# part5.net
KiCad netlist of a schematic drawn in Altium Designer
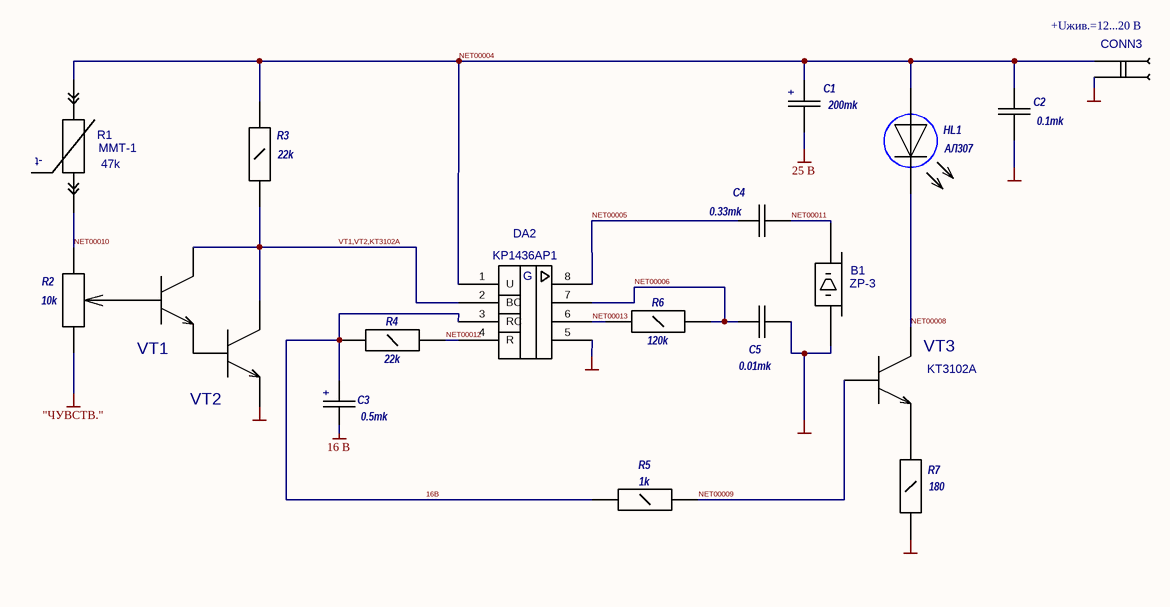
[diagram p0: part5.SCHDOC]

(export (version "E")
  (design (tool "Eeschema 10.0.6"))
  (components
    (comp (ref "B1") (value "ZP-3") (footprint "ЗП-3") (libsource (lib "*") (part "ZP-3")))
    (comp (ref "C1")
      (value "200mk")
      (footprint "К50-29 (17Х6)")
      (description "K50-29 (1;2,2;4,7;10;22 MK)")
      (libsource (lib "*") (part "K50-29 (1;2,2;4,7;10;22 MK)"))
    )
    (comp (ref "C2")
      (value "0.1mk")
      (footprint "K71-6 (10X4)")
      (description "K71-6 (5-30 МК)")
      (libsource (lib "*") (part "K71-6 (5-30 МК)"))
    )
    (comp (ref "C3")
      (value "0.5mk")
      (footprint "К50-29 (17Х6)")
      (description "K50-29 (1;2,2;4,7;10;22 MK)")
      (libsource (lib "*") (part "K50-29 (1;2,2;4,7;10;22 MK)"))
    )
    (comp (ref "C4")
      (value "0.33mk")
      (footprint "K71-6 (10X4)")
      (description "K71-6 (5-30 МК)")
      (libsource (lib "*") (part "K71-6 (5-30 МК)"))
    )
    (comp (ref "C5")
      (value "0.01mk")
      (footprint "K71-6 (10X4)")
      (description "K71-6 (5-30 МК)")
      (libsource (lib "*") (part "K71-6 (5-30 МК)"))
    )
    (comp (ref "CONN3")
      (value "+Uжив.=12...20 В")
      (footprint "CONN2X")
      (description "CONN2X")
      (libsource (lib "*") (part "CONN2X"))
    )
    (comp (ref "DA2") (value "KP1436AP1") (footprint "КР1436АП1") (libsource (lib "*") (part "KP1436AP1")))
    (comp (ref "HL1") (value "АЛ307") (footprint "АЛ307") (libsource (lib "*") (part "АЛ307")))
    (comp (ref "R1")
      (value "MMT-1")
      (footprint "MMT-1")
      (fields (field (name "ALTIUM_VALUE") "47k"))
      (libsource (lib "*") (part "MMT-1"))
    )
    (comp (ref "R2")
      (value "10k")
      (footprint "СП3-38В")
      (description "СП3-38В")
      (libsource (lib "*") (part "СП3-38В"))
    )
    (comp (ref "R3")
      (value "22k")
      (footprint "МЛТ(0.25)")
      (description "МЛТ(0.25)")
      (libsource (lib "*") (part "МЛТ(0.25)"))
    )
    (comp (ref "R4")
      (value "22k")
      (footprint "МЛТ(0.25)")
      (description "МЛТ(0.25)")
      (libsource (lib "*") (part "МЛТ(0.25)"))
    )
    (comp (ref "R5")
      (value "1k")
      (footprint "МЛТ(0.25)")
      (description "МЛТ(0.25)")
      (libsource (lib "*") (part "МЛТ(0.25)"))
    )
    (comp (ref "R6")
      (value "120k")
      (footprint "МЛТ(0.25)")
      (description "МЛТ(0.25)")
      (libsource (lib "*") (part "МЛТ(0.25)"))
    )
    (comp (ref "R7")
      (value "180")
      (footprint "МЛТ(0.25)")
      (description "МЛТ(0.25)")
      (libsource (lib "*") (part "МЛТ(0.25)"))
    )
    (comp (ref "VT1") (value "KT3102A") (footprint "KT3102A") (libsource (lib "*") (part "KT3102A")))
    (comp (ref "VT2") (value "KT3102A") (footprint "KT3102A") (libsource (lib "*") (part "KT3102A")))
    (comp (ref "VT3") (value "KT3102A") (footprint "KT3102A") (libsource (lib "*") (part "KT3102A")))
  )
  (nets
    (net (code "1") (name "\"ЧУВСТВ.\"") (class "Default")
      (node (ref "R2") (pin "2") (pinfunction "2_2") (pintype "passive"))
    )
    (net (code "2") (name "/16B") (class "Default")
      (node (ref "C3") (pin "2") (pinfunction "2_2") (pintype "passive"))
      (node (ref "DA2") (pin "3") (pinfunction "RC_3") (pintype "passive"))
      (node (ref "R4") (pin "1") (pinfunction "1_1") (pintype "passive"))
      (node (ref "R5") (pin "1") (pinfunction "1_1") (pintype "passive"))
    )
    (net (code "3") (name "/NET00004") (class "Default")
      (node (ref "C1") (pin "2") (pinfunction "2_2") (pintype "passive"))
      (node (ref "C2") (pin "2") (pinfunction "2_2") (pintype "passive"))
      (node (ref "CONN3") (pin "1") (pintype "passive"))
      (node (ref "DA2") (pin "1") (pinfunction "U_1") (pintype "passive"))
      (node (ref "HL1") (pin "1") (pinfunction "1_1") (pintype "passive"))
      (node (ref "R1") (pin "2") (pinfunction "2_2") (pintype "passive"))
      (node (ref "R3") (pin "1") (pinfunction "1_1") (pintype "passive"))
    )
    (net (code "4") (name "/NET00005") (class "Default")
      (node (ref "C4") (pin "2") (pinfunction "2_2") (pintype "passive"))
      (node (ref "DA2") (pin "8") (pintype "passive"))
    )
    (net (code "5") (name "/NET00006") (class "Default")
      (node (ref "C5") (pin "2") (pinfunction "2_2") (pintype "passive"))
      (node (ref "DA2") (pin "7") (pintype "passive"))
      (node (ref "R6") (pin "2") (pinfunction "2_2") (pintype "passive"))
    )
    (net (code "6") (name "/NET00008") (class "Default")
      (node (ref "HL1") (pin "2") (pinfunction "2_2") (pintype "passive"))
      (node (ref "VT3") (pin "3") (pinfunction "K_3") (pintype "passive"))
    )
    (net (code "7") (name "/NET00009") (class "Default")
      (node (ref "R5") (pin "2") (pinfunction "2_2") (pintype "passive"))
      (node (ref "VT3") (pin "2") (pinfunction "B_2") (pintype "passive"))
    )
    (net (code "8") (name "/NET00010") (class "Default")
      (node (ref "R1") (pin "1") (pinfunction "1_1") (pintype "passive"))
      (node (ref "R2") (pin "1") (pinfunction "1_1") (pintype "passive"))
    )
    (net (code "9") (name "/NET00011") (class "Default")
      (node (ref "B1") (pin "1") (pinfunction "1_1") (pintype "passive"))
      (node (ref "C4") (pin "1") (pinfunction "1_1") (pintype "passive"))
    )
    (net (code "10") (name "/NET00012") (class "Default")
      (node (ref "DA2") (pin "4") (pinfunction "R_4") (pintype "passive"))
      (node (ref "R4") (pin "2") (pinfunction "2_2") (pintype "passive"))
    )
    (net (code "11") (name "/NET00013") (class "Default")
      (node (ref "DA2") (pin "6") (pintype "passive"))
      (node (ref "R6") (pin "1") (pinfunction "1_1") (pintype "passive"))
    )
    (net (code "12") (name "/VT1,VT2,KT3102A") (class "Default")
      (node (ref "DA2") (pin "2") (pinfunction "BC_2") (pintype "passive"))
      (node (ref "R3") (pin "2") (pinfunction "2_2") (pintype "passive"))
      (node (ref "VT1") (pin "3") (pinfunction "K_3") (pintype "passive"))
      (node (ref "VT2") (pin "3") (pinfunction "K_3") (pintype "passive"))
    )
    (net (code "13") (name "16 В") (class "Default")
      (node (ref "C3") (pin "1") (pinfunction "1_1") (pintype "passive"))
    )
    (net (code "14") (name "25 В") (class "Default")
      (node (ref "C1") (pin "1") (pinfunction "1_1") (pintype "passive"))
    )
    (net (code "15") (name "<NO NET>") (class "Default")
      (node (ref "B1") (pin "2") (pinfunction "2_2") (pintype "passive"))
      (node (ref "C2") (pin "1") (pinfunction "1_1") (pintype "passive"))
      (node (ref "C5") (pin "1") (pinfunction "1_1") (pintype "passive"))
      (node (ref "CONN3") (pin "2") (pintype "passive"))
      (node (ref "DA2") (pin "5") (pintype "passive"))
      (node (ref "R7") (pin "2") (pinfunction "2_2") (pintype "passive"))
      (node (ref "VT2") (pin "1") (pinfunction "E_1") (pintype "passive"))
    )
    (net (code "16") (name "Net-(VT1-B)") (class "Default")
      (node (ref "R2") (pin "3") (pinfunction "3_3") (pintype "passive"))
      (node (ref "VT1") (pin "2") (pinfunction "B_2") (pintype "passive"))
    )
    (net (code "17") (name "Net-(VT1-E)") (class "Default")
      (node (ref "VT1") (pin "1") (pinfunction "E_1") (pintype "passive"))
      (node (ref "VT2") (pin "2") (pinfunction "B_2") (pintype "passive"))
    )
    (net (code "18") (name "Net-(VT3-E)") (class "Default")
      (node (ref "R7") (pin "1") (pinfunction "1_1") (pintype "passive"))
      (node (ref "VT3") (pin "1") (pinfunction "E_1") (pintype "passive"))
    )
  )
)
